# PR9025_B.net
KiCad netlist of a schematic drawn in EAGLE
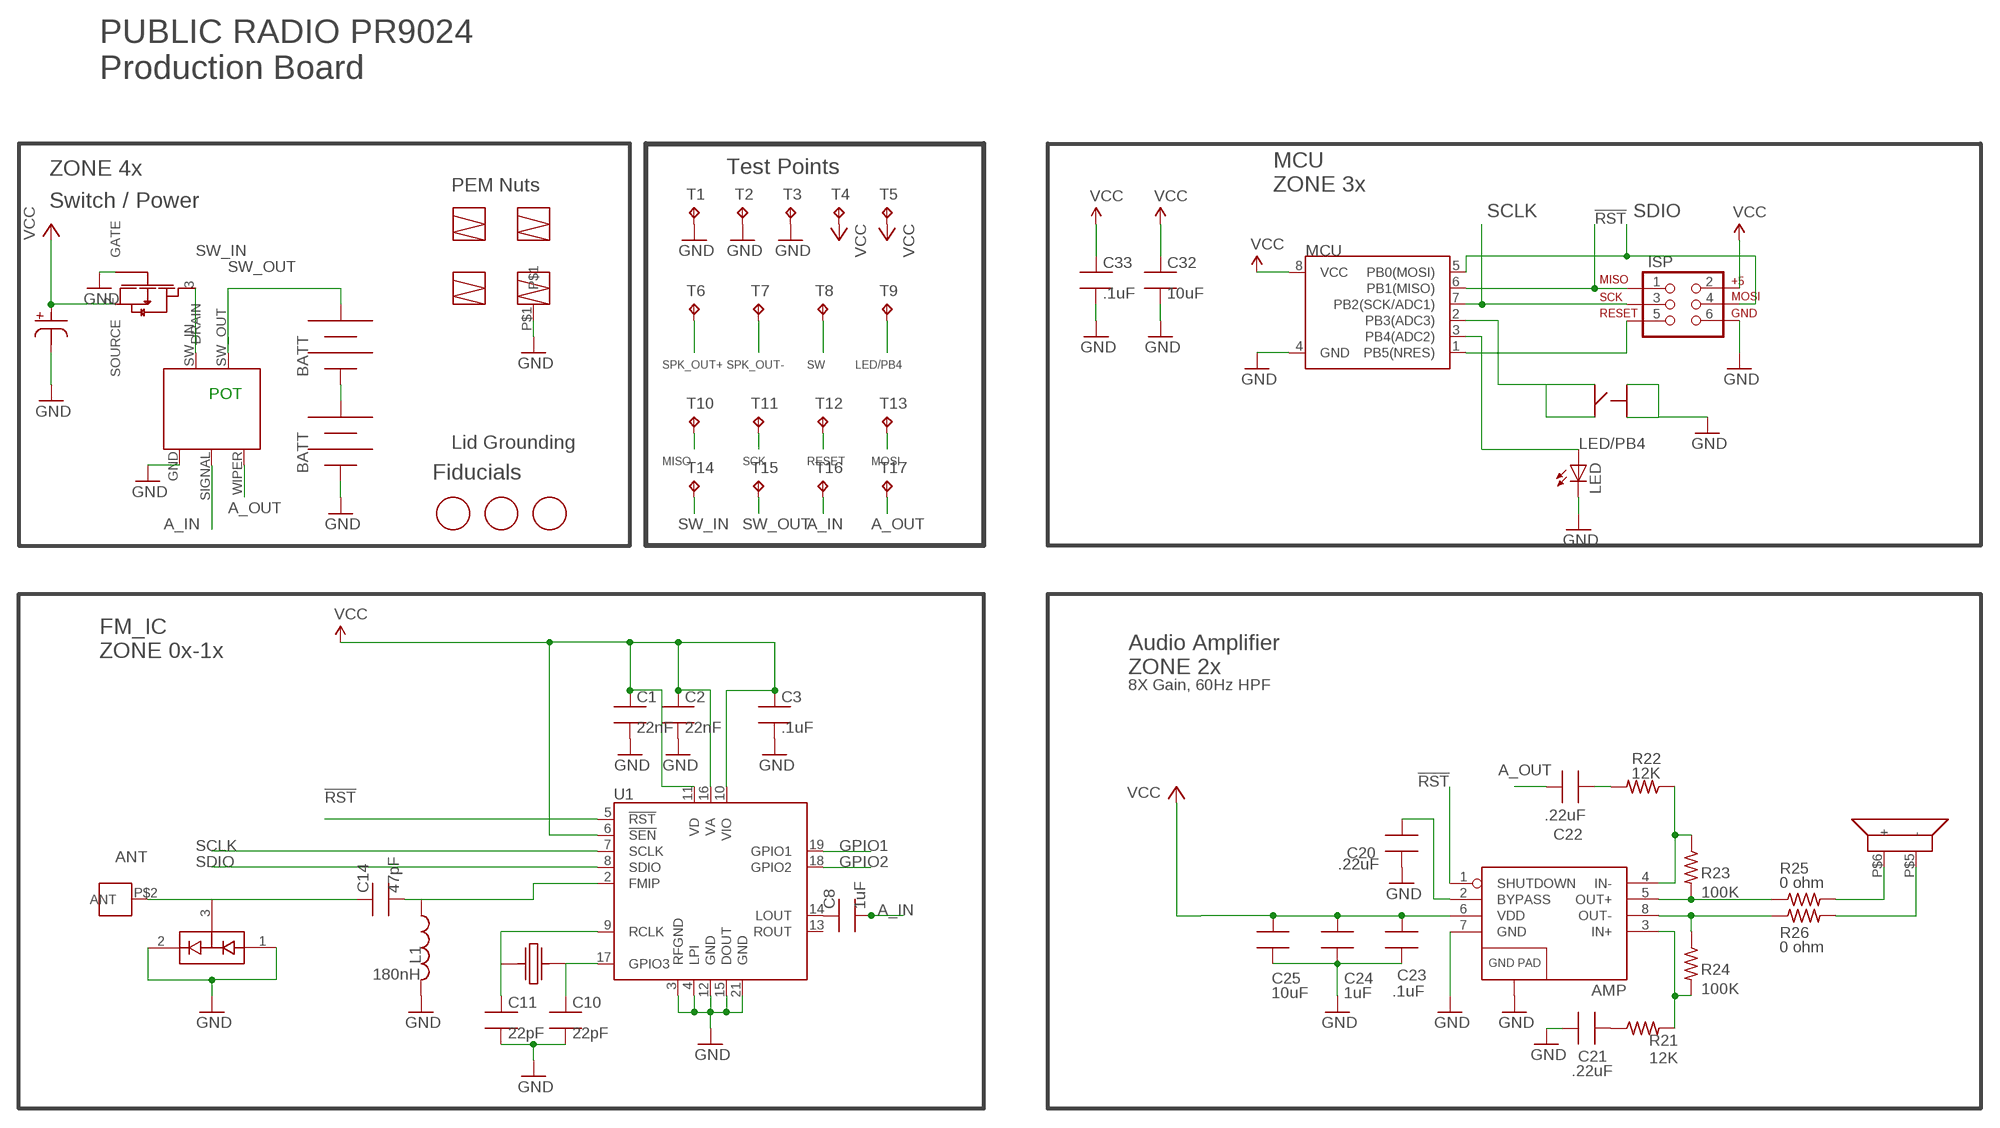
[diagram p0: schematic, sheet 1]

(export (version "E")
  (design (tool "Eeschema 10.0.6"))
  (components
    (comp (ref "AMP")
      (value "TPA6203A1")
      (footprint "eagle-import:8-MSOP")
      (libsource (lib "eagle-import") (part "TPA6203A1"))
    )
    (comp (ref "ANT_MOUNT")
      (value "DNP")
      (footprint "eagle-import:PEM_M3")
      (libsource (lib "eagle-import") (part "M3_PEMNUT"))
    )
    (comp (ref "C1")
      (value "22nF")
      (footprint "eagle-import:0603_CPL")
      (fields
        (field (name "MFG_PN") "CL10B223KB8NNNC")
        (field (name "TOL") "10%")
        (field (name "VOLTAGE") "16V")
      )
      (libsource (lib "eagle-import") (part "C_SMT_0603_CPL"))
    )
    (comp (ref "C2")
      (value "22nF")
      (footprint "eagle-import:0603_CPL")
      (fields
        (field (name "MFG_PN") "CL10B223KB8NNNC")
        (field (name "TOL") "10%")
        (field (name "VOLTAGE") "16V")
      )
      (libsource (lib "eagle-import") (part "C_SMT_0603_CPL"))
    )
    (comp (ref "C3")
      (value ".1uF")
      (footprint "eagle-import:0603_CPL")
      (fields
        (field (name "MFG_PN") "CL10B104KB8SFNC")
        (field (name "TOL") "10%")
        (field (name "VOLTAGE") "16V")
      )
      (libsource (lib "eagle-import") (part "C_SMT_0603_CPL"))
    )
    (comp (ref "C8")
      (value "1uF")
      (footprint "eagle-import:0603_CPL")
      (fields
        (field (name "MFG_PN") "CL10B105KP8NNNC")
        (field (name "TOL") "10%")
        (field (name "VOLTAGE") "10V")
      )
      (libsource (lib "eagle-import") (part "C_SMT_0603_CPL"))
    )
    (comp (ref "C10")
      (value "22pF")
      (footprint "eagle-import:0603_CPL")
      (fields
        (field (name "MFG_PN") "C1608C0G1H220J080AA")
        (field (name "TOL") "5%")
        (field (name "VOLTAGE") "50V")
      )
      (libsource (lib "eagle-import") (part "C_SMT_0603_CPL"))
    )
    (comp (ref "C11")
      (value "22pF")
      (footprint "eagle-import:0603_CPL")
      (fields
        (field (name "MFG_PN") "C1608C0G1H220J080AA")
        (field (name "TOL") "5%")
        (field (name "VOLTAGE") "50V")
      )
      (libsource (lib "eagle-import") (part "C_SMT_0603_CPL"))
    )
    (comp (ref "C14")
      (value "47pF")
      (footprint "eagle-import:0603_CPL")
      (fields
        (field (name "MFG_PN") "CL10C470JB8NCNC")
        (field (name "TOL") "5%")
        (field (name "VOLTAGE") "50V")
      )
      (libsource (lib "eagle-import") (part "C_SMT_0603_CPL"))
    )
    (comp (ref "C20")
      (value ".22uF")
      (footprint "eagle-import:0603_CPL")
      (fields
        (field (name "MFG_PN") "C1608X7R1C224K080AC")
        (field (name "TOL") "10%")
        (field (name "VOLTAGE") "16V")
      )
      (libsource (lib "eagle-import") (part "C_SMT_0603_CPL"))
    )
    (comp (ref "C21")
      (value ".22uF")
      (footprint "eagle-import:0603_CPL")
      (fields
        (field (name "MFG_PN") "C1608X7R1C224K080AC")
        (field (name "TOL") "10%")
        (field (name "VOLTAGE") "16V")
      )
      (libsource (lib "eagle-import") (part "C_SMT_0603_CPL"))
    )
    (comp (ref "C22")
      (value ".22uF")
      (footprint "eagle-import:0603_CPL")
      (fields
        (field (name "MFG_PN") "C1608X7R1C224K080AC")
        (field (name "TOL") "10%")
        (field (name "VOLTAGE") "16V")
      )
      (libsource (lib "eagle-import") (part "C_SMT_0603_CPL"))
    )
    (comp (ref "C23")
      (value ".1uF")
      (footprint "eagle-import:0603_CPL")
      (fields
        (field (name "MFG_PN") "CL10B104KB8SFNC")
        (field (name "TOL") "10%")
        (field (name "VOLTAGE") "16V")
      )
      (libsource (lib "eagle-import") (part "C_SMT_0603_CPL"))
    )
    (comp (ref "C24")
      (value "1uF")
      (footprint "eagle-import:0603_CPL")
      (fields
        (field (name "MFG_PN") "CL10B105KP8NNNC")
        (field (name "TOL") "10%")
        (field (name "VOLTAGE") "10V")
      )
      (libsource (lib "eagle-import") (part "C_SMT_0603_CPL"))
    )
    (comp (ref "C25")
      (value "10uF")
      (footprint "eagle-import:0603_CPL")
      (fields
        (field (name "MFG_PN") "CL10A106MQ8NNNC")
        (field (name "TOL") "20%")
        (field (name "VOLTAGE") "6.3V")
      )
      (libsource (lib "eagle-import") (part "C_SMT_0603_CPL"))
    )
    (comp (ref "C32")
      (value "10uF")
      (footprint "eagle-import:0603_CPL")
      (fields
        (field (name "MFG_PN") "CL10A106MQ8NNNC")
        (field (name "TOL") "20%")
        (field (name "VOLTAGE") "6.3V")
      )
      (libsource (lib "eagle-import") (part "C_SMT_0603_CPL"))
    )
    (comp (ref "C33")
      (value ".1uF")
      (footprint "eagle-import:0603_CPL")
      (fields
        (field (name "MFG_PN") "CL10B104KB8SFNC")
        (field (name "TOL") "10%")
        (field (name "VOLTAGE") "16V")
      )
      (libsource (lib "eagle-import") (part "C_SMT_0603_CPL"))
    )
    (comp (ref "C40")
      (value "220uF")
      (footprint "eagle-import:NICHICON_UD_63")
      (fields (field (name "TOL") "20%") (field (name "VOLTAGE") "16V"))
      (libsource (lib "eagle-import") (part "NICHICON_SERIESUD"))
    )
    (comp (ref "D1")
      (value "BAV99")
      (footprint "eagle-import:SOT23_CPL")
      (fields (field (name "MFG_PN") "BAV99,215"))
      (libsource (lib "eagle-import") (part "BAV99"))
    )
    (comp (ref "FET1")
      (value "AO3435")
      (footprint "eagle-import:SOT23_CPL")
      (fields (field (name "MFG_PN") "AO3435"))
      (libsource (lib "eagle-import") (part "AO3435"))
    )
    (comp (ref "ISP")
      (value "AVR_SPI_PRG_6NS")
      (footprint "eagle-import:2X3-NS")
      (libsource (lib "eagle-import") (part "AVR_SPI_PRG_6NS"))
    )
    (comp (ref "JP5")
      (value "BK-92_MPD_AA_BATT_CLIP")
      (footprint "eagle-import:BK92_AA_BATT")
      (fields (field (name "MFG_PN") "2 of BK92 - supplied by CL Labs"))
      (libsource (lib "eagle-import") (part "BK-92_MPD_AA_BATT_CLIP"))
    )
    (comp (ref "JP6")
      (value "BK-92_MPD_AA_BATT_CLIP")
      (footprint "eagle-import:BK92_AA_BATT")
      (fields (field (name "MFG_PN") "2 of BK92 - supplied by CL Labs"))
      (libsource (lib "eagle-import") (part "BK-92_MPD_AA_BATT_CLIP"))
    )
    (comp (ref "L1")
      (value "180nH")
      (footprint "eagle-import:0805_ADAFRUIT")
      (fields
        (field (name "CURRENT") "400mA")
        (field (name "DCR") "640m")
        (field (name "MFG_PN") "AISC-0805-R18J-T")
        (field (name "TOL") "5%")
      )
      (libsource (lib "eagle-import") (part "L_SMT_0805_ADAFRUIT"))
    )
    (comp (ref "LED")
      (value "HSMC-C265_REVERSE_MOUNT_LED")
      (footprint "eagle-import:HSMC-C265_REVERSE_MOUN_LED")
      (libsource (lib "eagle-import") (part "HSMC-C265_REVERSE_MOUNT_LED"))
    )
    (comp (ref "MARK1")
      (value "FIDUCIAL")
      (footprint "eagle-import:FIDUCIAL_1MM")
      (libsource (lib "eagle-import") (part "FIDUCIAL"))
    )
    (comp (ref "MARK2")
      (value "FIDUCIAL")
      (footprint "eagle-import:FIDUCIAL_1MM")
      (libsource (lib "eagle-import") (part "FIDUCIAL"))
    )
    (comp (ref "MARK3")
      (value "FIDUCIAL")
      (footprint "eagle-import:FIDUCIAL_1MM")
      (libsource (lib "eagle-import") (part "FIDUCIAL"))
    )
    (comp (ref "MCU")
      (value "ATTINY45TINY45-20-SMT")
      (footprint "eagle-import:8-SOIC")
      (libsource (lib "eagle-import") (part "ATTINY45TINY45-20-SMT"))
    )
    (comp (ref "R1")
      (value "VOLUME_POT")
      (footprint "eagle-import:H17112NS_A10K_L20F-002")
      (libsource (lib "eagle-import") (part "VOLUME_POT"))
    )
    (comp (ref "R21")
      (value "12K")
      (footprint "eagle-import:0603_CPL")
      (fields
        (field (name "MFG_PN") "RC0603FR-0712KL")
        (field (name "POWER") "1/10W")
        (field (name "TOL") "1%")
      )
      (libsource (lib "eagle-import") (part "R_SMT_R0603_CPL"))
    )
    (comp (ref "R22")
      (value "12K")
      (footprint "eagle-import:0603_CPL")
      (fields
        (field (name "MFG_PN") "RC0603FR-0712KL")
        (field (name "POWER") "1/10W")
        (field (name "TOL") "1%")
      )
      (libsource (lib "eagle-import") (part "R_SMT_R0603_CPL"))
    )
    (comp (ref "R23")
      (value "100K")
      (footprint "eagle-import:0603_CPL")
      (fields
        (field (name "MFG_PN") "ERJ-3EKF1003V")
        (field (name "POWER") "1/10W")
        (field (name "TOL") "1%")
      )
      (libsource (lib "eagle-import") (part "R_SMT_R0603_CPL"))
    )
    (comp (ref "R24")
      (value "100K")
      (footprint "eagle-import:0603_CPL")
      (fields
        (field (name "MFG_PN") "ERJ-3EKF1003V")
        (field (name "POWER") "1/10W")
        (field (name "TOL") "1%")
      )
      (libsource (lib "eagle-import") (part "R_SMT_R0603_CPL"))
    )
    (comp (ref "R25")
      (value "0 ohm")
      (footprint "eagle-import:0805_ADAFRUIT")
      (fields (field (name "MFG_PN") "ERJ-6GEY0R00V "))
      (libsource (lib "eagle-import") (part "R_SMT_0805_ADAFRUIT"))
    )
    (comp (ref "R26")
      (value "0 ohm")
      (footprint "eagle-import:0805_ADAFRUIT")
      (fields (field (name "MFG_PN") "ERJ-6GEY0R00V "))
      (libsource (lib "eagle-import") (part "R_SMT_0805_ADAFRUIT"))
    )
    (comp (ref "SPKR_PLACE")
      (value "DNP")
      (footprint "eagle-import:PR2024_SPKR_PLACE(SMD)")
      (libsource (lib "eagle-import") (part "PR2024_SPKR_SMD"))
    )
    (comp (ref "SW1")
      (value "C&K_PTS645")
      (footprint "eagle-import:C&K_PTS645_SMT")
      (libsource (lib "eagle-import") (part "C&K_PTS645"))
    )
    (comp (ref "T1")
      (value "TPTP20R")
      (footprint "eagle-import:TP20R")
      (libsource (lib "eagle-import") (part "TPTP20R"))
    )
    (comp (ref "T2")
      (value "TPTP20R")
      (footprint "eagle-import:TP20R")
      (libsource (lib "eagle-import") (part "TPTP20R"))
    )
    (comp (ref "T3")
      (value "TPTP20R")
      (footprint "eagle-import:TP20R")
      (libsource (lib "eagle-import") (part "TPTP20R"))
    )
    (comp (ref "T4")
      (value "TPTP20R")
      (footprint "eagle-import:TP20R")
      (libsource (lib "eagle-import") (part "TPTP20R"))
    )
    (comp (ref "T5")
      (value "TPTP20R")
      (footprint "eagle-import:TP20R")
      (libsource (lib "eagle-import") (part "TPTP20R"))
    )
    (comp (ref "T6")
      (value "TPTP20R")
      (footprint "eagle-import:TP20R")
      (libsource (lib "eagle-import") (part "TPTP20R"))
    )
    (comp (ref "T7")
      (value "TPTP20R")
      (footprint "eagle-import:TP20R")
      (libsource (lib "eagle-import") (part "TPTP20R"))
    )
    (comp (ref "T8")
      (value "TPTP20R")
      (footprint "eagle-import:TP20R")
      (libsource (lib "eagle-import") (part "TPTP20R"))
    )
    (comp (ref "T9")
      (value "TPTP20R")
      (footprint "eagle-import:TP20R")
      (libsource (lib "eagle-import") (part "TPTP20R"))
    )
    (comp (ref "T10")
      (value "TPTP20R")
      (footprint "eagle-import:TP20R")
      (libsource (lib "eagle-import") (part "TPTP20R"))
    )
    (comp (ref "T11")
      (value "TPTP20R")
      (footprint "eagle-import:TP20R")
      (libsource (lib "eagle-import") (part "TPTP20R"))
    )
    (comp (ref "T12")
      (value "TPTP20R")
      (footprint "eagle-import:TP20R")
      (libsource (lib "eagle-import") (part "TPTP20R"))
    )
    (comp (ref "T13")
      (value "TPTP20R")
      (footprint "eagle-import:TP20R")
      (libsource (lib "eagle-import") (part "TPTP20R"))
    )
    (comp (ref "T14")
      (value "TPTP20R")
      (footprint "eagle-import:TP20R")
      (libsource (lib "eagle-import") (part "TPTP20R"))
    )
    (comp (ref "T15")
      (value "TPTP20R")
      (footprint "eagle-import:TP20R")
      (libsource (lib "eagle-import") (part "TPTP20R"))
    )
    (comp (ref "T16")
      (value "TPTP20R")
      (footprint "eagle-import:TP20R")
      (libsource (lib "eagle-import") (part "TPTP20R"))
    )
    (comp (ref "T17")
      (value "TPTP20R")
      (footprint "eagle-import:TP20R")
      (libsource (lib "eagle-import") (part "TPTP20R"))
    )
    (comp (ref "U$2")
      (value "PEM_SMT")
      (footprint "eagle-import:PEM_SMT")
      (libsource (lib "eagle-import") (part "PEM_SMT"))
    )
    (comp (ref "U$3")
      (value "PEM_SMT")
      (footprint "eagle-import:PEM_SMT")
      (libsource (lib "eagle-import") (part "PEM_SMT"))
    )
    (comp (ref "U$4")
      (value "PEM_SMT")
      (footprint "eagle-import:PEM_SMT")
      (libsource (lib "eagle-import") (part "PEM_SMT"))
    )
    (comp (ref "U$5")
      (value "PEM_M3_SMT_W/PIN")
      (footprint "eagle-import:PEM_SMT")
      (libsource (lib "eagle-import") (part "PEM_M3_SMT_W/PIN"))
    )
    (comp (ref "U1")
      (value "SI4702-C19-GMR")
      (footprint "eagle-import:SI470X_20_QFN")
      (fields (field (name "MFG_PN") "Si4702 C19 GM - supplied by CL Labs"))
      (libsource (lib "eagle-import") (part "SI4702-C19-GMR"))
    )
    (comp (ref "X1")
      (value "ABS25XTAL")
      (footprint "eagle-import:4-SOJ")
      (libsource (lib "eagle-import") (part "ABS25XTAL"))
    )
  )
  (nets
    (net (code "1") (name "/ANT") (class "Default")
      (node (ref "ANT_MOUNT") (pin "P$2") (pinfunction "ANT_P$2") (pintype "bidirectional"))
      (node (ref "C14") (pin "1") (pinfunction "1_1") (pintype "passive"))
      (node (ref "D1") (pin "3") (pinfunction "COM_3") (pintype "bidirectional"))
    )
    (net (code "2") (name "/A_IN") (class "Default")
      (node (ref "C8") (pin "2") (pinfunction "2_2") (pintype "passive"))
      (node (ref "R1") (pin "SIGNAL") (pinfunction "SIGNAL_SIGNAL") (pintype "bidirectional"))
      (node (ref "T16") (pin "TP") (pinfunction "TP_TP") (pintype "input"))
    )
    (net (code "3") (name "/A_OUT") (class "Default")
      (node (ref "C22") (pin "2") (pinfunction "2_2") (pintype "passive"))
      (node (ref "R1") (pin "WIPER") (pinfunction "WIPER_WIPER") (pintype "bidirectional"))
      (node (ref "T17") (pin "TP") (pinfunction "TP_TP") (pintype "input"))
    )
    (net (code "4") (name "/GPIO1") (class "Default")
      (node (ref "U1") (pin "19") (pinfunction "GPIO1_19") (pintype "bidirectional"))
    )
    (net (code "5") (name "/GPIO2") (class "Default")
      (node (ref "U1") (pin "18") (pinfunction "GPIO2_18") (pintype "bidirectional"))
    )
    (net (code "6") (name "/LED{slash}PB4") (class "Default")
      (node (ref "LED") (pin "P$1") (pinfunction "A_P$1") (pintype "passive"))
      (node (ref "MCU") (pin "3") (pinfunction "PB4(ADC2)_3") (pintype "bidirectional"))
      (node (ref "T9") (pin "TP") (pinfunction "TP_TP") (pintype "input"))
    )
    (net (code "7") (name "/RESET") (class "Default")
      (node (ref "ISP") (pin "5") (pinfunction "5_5") (pintype "passive"))
      (node (ref "MCU") (pin "1") (pinfunction "PB5(NRES)_1") (pintype "bidirectional"))
      (node (ref "T12") (pin "TP") (pinfunction "TP_TP") (pintype "input"))
    )
    (net (code "8") (name "/SCLK") (class "Default")
      (node (ref "ISP") (pin "3") (pinfunction "3_3") (pintype "passive"))
      (node (ref "MCU") (pin "7") (pinfunction "PB2(SCK/ADC1)_7") (pintype "bidirectional"))
      (node (ref "T11") (pin "TP") (pinfunction "TP_TP") (pintype "input"))
      (node (ref "U1") (pin "7") (pinfunction "SCLK_7") (pintype "bidirectional"))
    )
    (net (code "9") (name "/SDIO") (class "Default")
      (node (ref "ISP") (pin "4") (pinfunction "4_4") (pintype "passive"))
      (node (ref "MCU") (pin "5") (pinfunction "PB0(MOSI)_5") (pintype "bidirectional"))
      (node (ref "T13") (pin "TP") (pinfunction "TP_TP") (pintype "input"))
      (node (ref "U1") (pin "8") (pinfunction "SDIO_8") (pintype "bidirectional"))
    )
    (net (code "10") (name "/SPK_OUT+") (class "Default")
      (node (ref "R25") (pin "2") (pinfunction "2_2") (pintype "passive"))
      (node (ref "SPKR_PLACE") (pin "P$6") (pinfunction "+_P$6") (pintype "bidirectional"))
      (node (ref "T6") (pin "TP") (pinfunction "TP_TP") (pintype "input"))
    )
    (net (code "11") (name "/SPK_OUT-") (class "Default")
      (node (ref "R26") (pin "2") (pinfunction "2_2") (pintype "passive"))
      (node (ref "SPKR_PLACE") (pin "P$5") (pinfunction "-_P$5") (pintype "bidirectional"))
      (node (ref "T7") (pin "TP") (pinfunction "TP_TP") (pintype "input"))
    )
    (net (code "12") (name "/SW") (class "Default")
      (node (ref "MCU") (pin "2") (pinfunction "PB3(ADC3)_2") (pintype "bidirectional"))
      (node (ref "SW1") (pin "P$3") (pinfunction "P$3_P$3") (pintype "bidirectional"))
      (node (ref "SW1") (pin "P$4") (pinfunction "P$4_P$4") (pintype "bidirectional"))
      (node (ref "T8") (pin "TP") (pinfunction "TP_TP") (pintype "input"))
    )
    (net (code "13") (name "/SW_IN") (class "Default")
      (node (ref "FET1") (pin "3") (pinfunction "DRAIN_3") (pintype "bidirectional"))
      (node (ref "R1") (pin "SW_IN") (pinfunction "SW_IN_SW_IN") (pintype "bidirectional"))
      (node (ref "T14") (pin "TP") (pinfunction "TP_TP") (pintype "input"))
    )
    (net (code "14") (name "/SW_OUT") (class "Default")
      (node (ref "JP5") (pin "POS") (pinfunction "POS_POS") (pintype "bidirectional"))
      (node (ref "JP5") (pin "POS@2") (pinfunction "POS_POS@2") (pintype "bidirectional"))
      (node (ref "R1") (pin "SW_OUT") (pinfunction "SW_OUT_SW_OUT") (pintype "bidirectional"))
      (node (ref "T15") (pin "TP") (pinfunction "TP_TP") (pintype "input"))
    )
    (net (code "15") (name "/~{RST}") (class "Default")
      (node (ref "AMP") (pin "1") (pinfunction "SHUTDOWN_1") (pintype "input"))
      (node (ref "ISP") (pin "1") (pinfunction "1_1") (pintype "passive"))
      (node (ref "MCU") (pin "6") (pinfunction "PB1(MISO)_6") (pintype "bidirectional"))
      (node (ref "T10") (pin "TP") (pinfunction "TP_TP") (pintype "input"))
      (node (ref "U1") (pin "5") (pinfunction "~{RST}_5") (pintype "bidirectional"))
    )
    (net (code "16") (name "GND") (class "Default")
      (node (ref "AMP") (pin "7") (pinfunction "GND_7") (pintype "power_in"))
      (node (ref "AMP") (pin "9") (pinfunction "GND_9") (pintype "power_in"))
      (node (ref "C1") (pin "2") (pinfunction "2_2") (pintype "passive"))
      (node (ref "C10") (pin "2") (pinfunction "2_2") (pintype "passive"))
      (node (ref "C11") (pin "2") (pinfunction "2_2") (pintype "passive"))
      (node (ref "C2") (pin "2") (pinfunction "2_2") (pintype "passive"))
      (node (ref "C20") (pin "1") (pinfunction "1_1") (pintype "passive"))
      (node (ref "C21") (pin "1") (pinfunction "1_1") (pintype "passive"))
      (node (ref "C23") (pin "2") (pinfunction "2_2") (pintype "passive"))
      (node (ref "C24") (pin "2") (pinfunction "2_2") (pintype "passive"))
      (node (ref "C25") (pin "2") (pinfunction "2_2") (pintype "passive"))
      (node (ref "C3") (pin "2") (pinfunction "2_2") (pintype "passive"))
      (node (ref "C32") (pin "2") (pinfunction "2_2") (pintype "passive"))
      (node (ref "C33") (pin "2") (pinfunction "2_2") (pintype "passive"))
      (node (ref "C40") (pin "P$2") (pinfunction "P$2_P$2") (pintype "bidirectional"))
      (node (ref "D1") (pin "1") (pinfunction "A1_1") (pintype "bidirectional"))
      (node (ref "D1") (pin "2") (pinfunction "C2_2") (pintype "bidirectional"))
      (node (ref "FET1") (pin "1") (pinfunction "GATE_1") (pintype "bidirectional"))
      (node (ref "ISP") (pin "6") (pinfunction "6_6") (pintype "passive"))
      (node (ref "JP6") (pin "NEG") (pinfunction "NEG_NEG") (pintype "bidirectional"))
      (node (ref "JP6") (pin "NEG@2") (pinfunction "NEG_NEG@2") (pintype "bidirectional"))
      (node (ref "L1") (pin "2") (pinfunction "2_2") (pintype "passive"))
      (node (ref "LED") (pin "P$2") (pinfunction "C_P$2") (pintype "passive"))
      (node (ref "MCU") (pin "4") (pinfunction "GND_4") (pintype "bidirectional"))
      (node (ref "R1") (pin "GND") (pinfunction "GND_GND") (pintype "bidirectional"))
      (node (ref "SW1") (pin "P$1") (pinfunction "P$1_P$1") (pintype "bidirectional"))
      (node (ref "SW1") (pin "P$2") (pinfunction "P$2_P$2") (pintype "bidirectional"))
      (node (ref "T1") (pin "TP") (pinfunction "TP_TP") (pintype "input"))
      (node (ref "T2") (pin "TP") (pinfunction "TP_TP") (pintype "input"))
      (node (ref "T3") (pin "TP") (pinfunction "TP_TP") (pintype "input"))
      (node (ref "U$5") (pin "P$1") (pinfunction "P$1_P$1") (pintype "bidirectional"))
      (node (ref "U1") (pin "12") (pinfunction "GND_12") (pintype "bidirectional"))
      (node (ref "U1") (pin "15") (pinfunction "DOUT_15") (pintype "bidirectional"))
      (node (ref "U1") (pin "21") (pinfunction "GND_21") (pintype "bidirectional"))
      (node (ref "U1") (pin "3") (pinfunction "RFGND_3") (pintype "bidirectional"))
      (node (ref "U1") (pin "4") (pinfunction "LPI_4") (pintype "bidirectional"))
    )
    (net (code "17") (name "Net-(AMP-BYPASS)") (class "Default")
      (node (ref "AMP") (pin "2") (pinfunction "BYPASS_2") (pintype "bidirectional"))
      (node (ref "C20") (pin "2") (pinfunction "2_2") (pintype "passive"))
    )
    (net (code "18") (name "Net-(AMP-IN+)") (class "Default")
      (node (ref "AMP") (pin "3") (pinfunction "IN+_3") (pintype "bidirectional"))
      (node (ref "R21") (pin "2") (pinfunction "2_2") (pintype "passive"))
      (node (ref "R24") (pin "2") (pinfunction "2_2") (pintype "passive"))
    )
    (net (code "19") (name "Net-(AMP-IN-)") (class "Default")
      (node (ref "AMP") (pin "4") (pinfunction "IN-_4") (pintype "bidirectional"))
      (node (ref "R22") (pin "1") (pinfunction "1_1") (pintype "passive"))
      (node (ref "R23") (pin "1") (pinfunction "1_1") (pintype "passive"))
    )
    (net (code "20") (name "Net-(AMP-OUT+)") (class "Default")
      (node (ref "AMP") (pin "5") (pinfunction "OUT+_5") (pintype "bidirectional"))
      (node (ref "R23") (pin "2") (pinfunction "2_2") (pintype "passive"))
      (node (ref "R25") (pin "1") (pinfunction "1_1") (pintype "passive"))
    )
    (net (code "21") (name "Net-(AMP-OUT-)") (class "Default")
      (node (ref "AMP") (pin "8") (pinfunction "OUT-_8") (pintype "bidirectional"))
      (node (ref "R24") (pin "1") (pinfunction "1_1") (pintype "passive"))
      (node (ref "R26") (pin "1") (pinfunction "1_1") (pintype "passive"))
    )
    (net (code "22") (name "Net-(C21-Pad2)") (class "Default")
      (node (ref "C21") (pin "2") (pinfunction "2_2") (pintype "passive"))
      (node (ref "R21") (pin "1") (pinfunction "1_1") (pintype "passive"))
    )
    (net (code "23") (name "Net-(C22-Pad1)") (class "Default")
      (node (ref "C22") (pin "1") (pinfunction "1_1") (pintype "passive"))
      (node (ref "R22") (pin "2") (pinfunction "2_2") (pintype "passive"))
    )
    (net (code "24") (name "Net-(JP5-NEG-PadNEG@2)") (class "Default")
      (node (ref "JP5") (pin "NEG") (pinfunction "NEG_NEG") (pintype "bidirectional"))
      (node (ref "JP5") (pin "NEG@2") (pinfunction "NEG_NEG@2") (pintype "bidirectional"))
      (node (ref "JP6") (pin "POS") (pinfunction "POS_POS") (pintype "bidirectional"))
      (node (ref "JP6") (pin "POS@2") (pinfunction "POS_POS@2") (pintype "bidirectional"))
    )
    (net (code "25") (name "Net-(U1-FMIP)") (class "Default")
      (node (ref "C14") (pin "2") (pinfunction "2_2") (pintype "passive"))
      (node (ref "L1") (pin "1") (pinfunction "1_1") (pintype "passive"))
      (node (ref "U1") (pin "2") (pinfunction "FMIP_2") (pintype "bidirectional"))
    )
    (net (code "26") (name "Net-(U1-GPIO3)") (class "Default")
      (node (ref "C10") (pin "1") (pinfunction "1_1") (pintype "passive"))
      (node (ref "U1") (pin "17") (pinfunction "GPIO3_17") (pintype "bidirectional"))
      (node (ref "X1") (pin "P$4") (pinfunction "P$4_P$4") (pintype "bidirectional"))
    )
    (net (code "27") (name "Net-(U1-LOUT)") (class "Default")
      (node (ref "C8") (pin "1") (pinfunction "1_1") (pintype "passive"))
      (node (ref "U1") (pin "14") (pinfunction "LOUT_14") (pintype "bidirectional"))
    )
    (net (code "28") (name "Net-(U1-RCLK)") (class "Default")
      (node (ref "C11") (pin "1") (pinfunction "1_1") (pintype "passive"))
      (node (ref "U1") (pin "9") (pinfunction "RCLK_9") (pintype "bidirectional"))
      (node (ref "X1") (pin "P$1") (pinfunction "P$1_P$1") (pintype "bidirectional"))
    )
    (net (code "29") (name "VCC") (class "Default")
      (node (ref "AMP") (pin "6") (pinfunction "VDD_6") (pintype "power_in"))
      (node (ref "C1") (pin "1") (pinfunction "1_1") (pintype "passive"))
      (node (ref "C2") (pin "1") (pinfunction "1_1") (pintype "passive"))
      (node (ref "C23") (pin "1") (pinfunction "1_1") (pintype "passive"))
      (node (ref "C24") (pin "1") (pinfunction "1_1") (pintype "passive"))
      (node (ref "C25") (pin "1") (pinfunction "1_1") (pintype "passive"))
      (node (ref "C3") (pin "1") (pinfunction "1_1") (pintype "passive"))
      (node (ref "C32") (pin "1") (pinfunction "1_1") (pintype "passive"))
      (node (ref "C33") (pin "1") (pinfunction "1_1") (pintype "passive"))
      (node (ref "C40") (pin "P$1") (pinfunction "P$1_P$1") (pintype "bidirectional"))
      (node (ref "FET1") (pin "2") (pinfunction "SOURCE_2") (pintype "bidirectional"))
      (node (ref "ISP") (pin "2") (pinfunction "2_2") (pintype "passive"))
      (node (ref "MCU") (pin "8") (pinfunction "VCC_8") (pintype "bidirectional"))
      (node (ref "T4") (pin "TP") (pinfunction "TP_TP") (pintype "input"))
      (node (ref "T5") (pin "TP") (pinfunction "TP_TP") (pintype "input"))
      (node (ref "U1") (pin "10") (pinfunction "VIO_10") (pintype "bidirectional"))
      (node (ref "U1") (pin "11") (pinfunction "VD_11") (pintype "bidirectional"))
      (node (ref "U1") (pin "16") (pinfunction "VA_16") (pintype "bidirectional"))
      (node (ref "U1") (pin "6") (pinfunction "~{SEN}_6") (pintype "bidirectional"))
    )
    (net (code "30") (name "unconnected-(U1-ROUT-Pad13)") (class "Default")
      (node (ref "U1") (pin "13") (pinfunction "ROUT_13") (pintype "bidirectional"))
    )
  )
)
